# encoder-hex-trigg.net
KiCad netlist of a schematic drawn in EAGLE
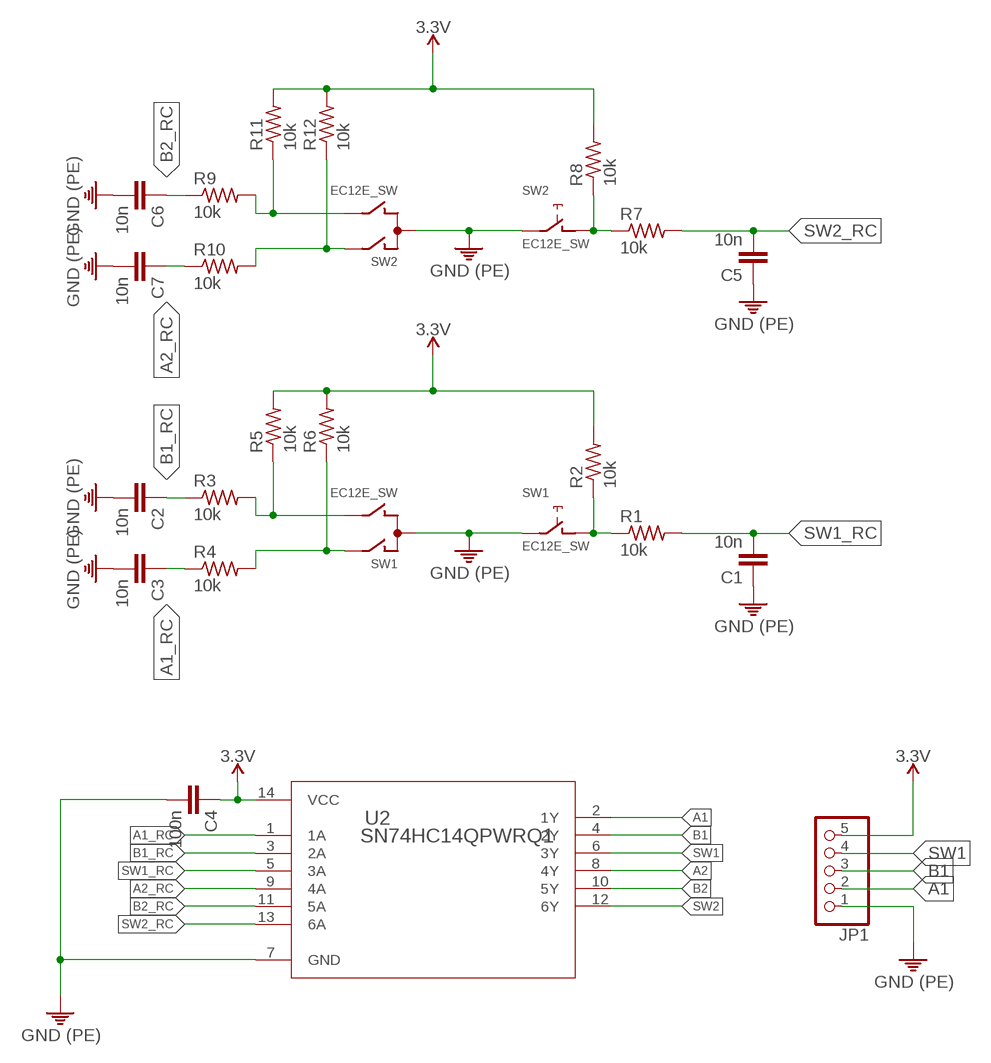
[diagram p0: schematic, sheet 1]

(export (version "E")
  (design (tool "Eeschema 10.0.6"))
  (components
    (comp (ref "C1")
      (value "10n")
      (footprint "eagle-import:C0603")
      (libsource (lib "eagle-import") (part "C-EUC0603"))
    )
    (comp (ref "C2")
      (value "10n")
      (footprint "eagle-import:C0603")
      (libsource (lib "eagle-import") (part "C-EUC0603"))
    )
    (comp (ref "C3")
      (value "10n")
      (footprint "eagle-import:C0603")
      (libsource (lib "eagle-import") (part "C-EUC0603"))
    )
    (comp (ref "C4")
      (value "100n")
      (footprint "eagle-import:C0603")
      (libsource (lib "eagle-import") (part "C-EUC0603"))
    )
    (comp (ref "C5")
      (value "10n")
      (footprint "eagle-import:C0603")
      (libsource (lib "eagle-import") (part "C-EUC0603"))
    )
    (comp (ref "C6")
      (value "10n")
      (footprint "eagle-import:C0603")
      (libsource (lib "eagle-import") (part "C-EUC0603"))
    )
    (comp (ref "C7")
      (value "10n")
      (footprint "eagle-import:C0603")
      (libsource (lib "eagle-import") (part "C-EUC0603"))
    )
    (comp (ref "JP1")
      (value "PINHD-1X5")
      (footprint "eagle-import:1X05")
      (libsource (lib "eagle-import") (part "PINHD-1X5"))
    )
    (comp (ref "R1")
      (value "10k")
      (footprint "eagle-import:R0603")
      (libsource (lib "eagle-import") (part "R-US_R0603"))
    )
    (comp (ref "R2")
      (value "10k")
      (footprint "eagle-import:R0603")
      (libsource (lib "eagle-import") (part "R-US_R0603"))
    )
    (comp (ref "R3")
      (value "10k")
      (footprint "eagle-import:R0603")
      (libsource (lib "eagle-import") (part "R-US_R0603"))
    )
    (comp (ref "R4")
      (value "10k")
      (footprint "eagle-import:R0603")
      (libsource (lib "eagle-import") (part "R-US_R0603"))
    )
    (comp (ref "R5")
      (value "10k")
      (footprint "eagle-import:R0603")
      (libsource (lib "eagle-import") (part "R-US_R0603"))
    )
    (comp (ref "R6")
      (value "10k")
      (footprint "eagle-import:R0603")
      (libsource (lib "eagle-import") (part "R-US_R0603"))
    )
    (comp (ref "R7")
      (value "10k")
      (footprint "eagle-import:R0603")
      (libsource (lib "eagle-import") (part "R-US_R0603"))
    )
    (comp (ref "R8")
      (value "10k")
      (footprint "eagle-import:R0603")
      (libsource (lib "eagle-import") (part "R-US_R0603"))
    )
    (comp (ref "R9")
      (value "10k")
      (footprint "eagle-import:R0603")
      (libsource (lib "eagle-import") (part "R-US_R0603"))
    )
    (comp (ref "R10")
      (value "10k")
      (footprint "eagle-import:R0603")
      (libsource (lib "eagle-import") (part "R-US_R0603"))
    )
    (comp (ref "R11")
      (value "10k")
      (footprint "eagle-import:R0603")
      (libsource (lib "eagle-import") (part "R-US_R0603"))
    )
    (comp (ref "R12")
      (value "10k")
      (footprint "eagle-import:R0603")
      (libsource (lib "eagle-import") (part "R-US_R0603"))
    )
    (comp (ref "SW1")
      (value "EC12E_SW")
      (footprint "eagle-import:ALPS_EC12E_SW")
      (fields (field (name "MPN") "EC12E2424407"))
      (libsource (lib "eagle-import") (part "EC12E_SW"))
    )
    (comp (ref "SW2")
      (value "EC12E_SW")
      (footprint "eagle-import:ALPS_EC12E_SW")
      (fields (field (name "MPN") "EC12E2424407"))
      (libsource (lib "eagle-import") (part "EC12E_SW"))
    )
    (comp (ref "U2")
      (value "SN74HC14QPWRQ1")
      (footprint "eagle-import:PW14")
      (fields (field (name "COPYRIGHT") "Copyright (C) 2022 Ultra Librarian. All rights reserved."))
      (libsource (lib "eagle-import") (part "SN74HC14QPWRQ1"))
    )
  )
  (nets
    (net (code "1") (name "3.3V") (class "Default")
      (node (ref "C4") (pin "1") (pinfunction "1_1") (pintype "passive"))
      (node (ref "JP1") (pin "5") (pinfunction "5_5") (pintype "passive"))
      (node (ref "R11") (pin "2") (pinfunction "2_2") (pintype "passive"))
      (node (ref "R12") (pin "2") (pinfunction "2_2") (pintype "passive"))
      (node (ref "R2") (pin "2") (pinfunction "2_2") (pintype "passive"))
      (node (ref "R5") (pin "2") (pinfunction "2_2") (pintype "passive"))
      (node (ref "R6") (pin "2") (pinfunction "2_2") (pintype "passive"))
      (node (ref "R8") (pin "2") (pinfunction "2_2") (pintype "passive"))
      (node (ref "U2") (pin "14") (pinfunction "VCC_14") (pintype "power_in"))
    )
    (net (code "2") (name "A1") (class "Default")
      (node (ref "JP1") (pin "2") (pinfunction "2_2") (pintype "passive"))
      (node (ref "U2") (pin "2") (pinfunction "1Y_2") (pintype "output"))
    )
    (net (code "3") (name "A1_RC") (class "Default")
      (node (ref "C3") (pin "1") (pinfunction "1_1") (pintype "passive"))
      (node (ref "R4") (pin "1") (pinfunction "1_1") (pintype "passive"))
      (node (ref "U2") (pin "1") (pinfunction "1A_1") (pintype "input"))
    )
    (net (code "4") (name "A2") (class "Default")
      (node (ref "U2") (pin "8") (pinfunction "4Y_8") (pintype "output"))
    )
    (net (code "5") (name "A2_RC") (class "Default")
      (node (ref "C7") (pin "1") (pinfunction "1_1") (pintype "passive"))
      (node (ref "R10") (pin "1") (pinfunction "1_1") (pintype "passive"))
      (node (ref "U2") (pin "9") (pinfunction "4A_9") (pintype "input"))
    )
    (net (code "6") (name "B1") (class "Default")
      (node (ref "JP1") (pin "3") (pinfunction "3_3") (pintype "passive"))
      (node (ref "U2") (pin "4") (pinfunction "2Y_4") (pintype "output"))
    )
    (net (code "7") (name "B1_RC") (class "Default")
      (node (ref "C2") (pin "1") (pinfunction "1_1") (pintype "passive"))
      (node (ref "R3") (pin "1") (pinfunction "1_1") (pintype "passive"))
      (node (ref "U2") (pin "3") (pinfunction "2A_3") (pintype "input"))
    )
    (net (code "8") (name "B2") (class "Default")
      (node (ref "U2") (pin "10") (pinfunction "5Y_10") (pintype "output"))
    )
    (net (code "9") (name "B2_RC") (class "Default")
      (node (ref "C6") (pin "1") (pinfunction "1_1") (pintype "passive"))
      (node (ref "R9") (pin "1") (pinfunction "1_1") (pintype "passive"))
      (node (ref "U2") (pin "11") (pinfunction "5A_11") (pintype "input"))
    )
    (net (code "10") (name "Net-(R3-Pad2)") (class "Default")
      (node (ref "R3") (pin "2") (pinfunction "2_2") (pintype "passive"))
      (node (ref "R5") (pin "1") (pinfunction "1_1") (pintype "passive"))
      (node (ref "SW1") (pin "B") (pinfunction "B_B") (pintype "passive"))
    )
    (net (code "11") (name "Net-(R4-Pad2)") (class "Default")
      (node (ref "R4") (pin "2") (pinfunction "2_2") (pintype "passive"))
      (node (ref "R6") (pin "1") (pinfunction "1_1") (pintype "passive"))
      (node (ref "SW1") (pin "A") (pinfunction "A_A") (pintype "passive"))
    )
    (net (code "12") (name "Net-(R10-Pad2)") (class "Default")
      (node (ref "R10") (pin "2") (pinfunction "2_2") (pintype "passive"))
      (node (ref "R12") (pin "1") (pinfunction "1_1") (pintype "passive"))
      (node (ref "SW2") (pin "A") (pinfunction "A_A") (pintype "passive"))
    )
    (net (code "13") (name "Net-(R11-Pad1)") (class "Default")
      (node (ref "R11") (pin "1") (pinfunction "1_1") (pintype "passive"))
      (node (ref "R9") (pin "2") (pinfunction "2_2") (pintype "passive"))
      (node (ref "SW2") (pin "B") (pinfunction "B_B") (pintype "passive"))
    )
    (net (code "14") (name "Net-(SW1B-1)") (class "Default")
      (node (ref "R1") (pin "1") (pinfunction "1_1") (pintype "passive"))
      (node (ref "R2") (pin "1") (pinfunction "1_1") (pintype "passive"))
      (node (ref "SW1") (pin "D") (pinfunction "1_D") (pintype "passive"))
    )
    (net (code "15") (name "Net-(SW2B-1)") (class "Default")
      (node (ref "R7") (pin "1") (pinfunction "1_1") (pintype "passive"))
      (node (ref "R8") (pin "1") (pinfunction "1_1") (pintype "passive"))
      (node (ref "SW2") (pin "D") (pinfunction "1_D") (pintype "passive"))
    )
    (net (code "16") (name "POWER-GND") (class "Default")
      (node (ref "C1") (pin "1") (pinfunction "1_1") (pintype "passive"))
      (node (ref "C2") (pin "2") (pinfunction "2_2") (pintype "passive"))
      (node (ref "C3") (pin "2") (pinfunction "2_2") (pintype "passive"))
      (node (ref "C4") (pin "2") (pinfunction "2_2") (pintype "passive"))
      (node (ref "C5") (pin "1") (pinfunction "1_1") (pintype "passive"))
      (node (ref "C6") (pin "2") (pinfunction "2_2") (pintype "passive"))
      (node (ref "C7") (pin "2") (pinfunction "2_2") (pintype "passive"))
      (node (ref "JP1") (pin "1") (pinfunction "1_1") (pintype "passive"))
      (node (ref "SW1") (pin "C") (pinfunction "C_C") (pintype "passive"))
      (node (ref "SW1") (pin "E") (pinfunction "2_E") (pintype "passive"))
      (node (ref "SW2") (pin "C") (pinfunction "C_C") (pintype "passive"))
      (node (ref "SW2") (pin "E") (pinfunction "2_E") (pintype "passive"))
      (node (ref "U2") (pin "7") (pinfunction "GND_7") (pintype "power_in"))
    )
    (net (code "17") (name "SW1") (class "Default")
      (node (ref "JP1") (pin "4") (pinfunction "4_4") (pintype "passive"))
      (node (ref "U2") (pin "6") (pinfunction "3Y_6") (pintype "output"))
    )
    (net (code "18") (name "SW1_RC") (class "Default")
      (node (ref "C1") (pin "2") (pinfunction "2_2") (pintype "passive"))
      (node (ref "R1") (pin "2") (pinfunction "2_2") (pintype "passive"))
      (node (ref "U2") (pin "5") (pinfunction "3A_5") (pintype "input"))
    )
    (net (code "19") (name "SW2") (class "Default")
      (node (ref "U2") (pin "12") (pinfunction "6Y_12") (pintype "output"))
    )
    (net (code "20") (name "SW2_RC") (class "Default")
      (node (ref "C5") (pin "2") (pinfunction "2_2") (pintype "passive"))
      (node (ref "R7") (pin "2") (pinfunction "2_2") (pintype "passive"))
      (node (ref "U2") (pin "13") (pinfunction "6A_13") (pintype "input"))
    )
  )
)
